# RECEPTORA_SECUNDARIA.net
KiCad netlist of a schematic drawn in Altium Designer
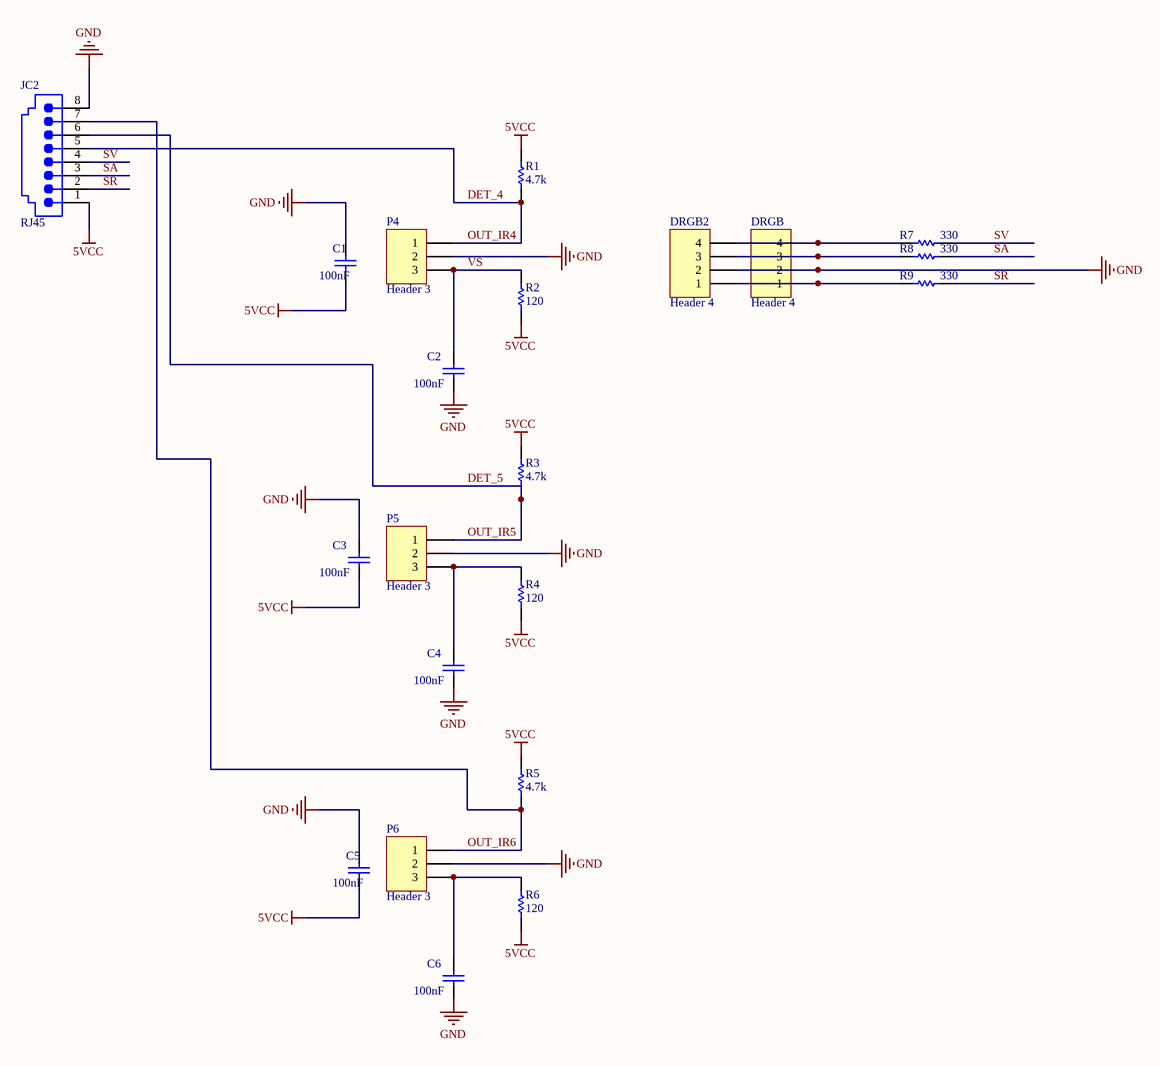
[diagram p0: RECEPTORA_SECUNDARIA.SchDoc]

(export (version "E")
  (design (tool "Eeschema 10.0.6"))
  (components
    (comp (ref "C1")
      (value "100nF")
      (footprint "VP44-2.5")
      (description "Dipped Radial Multilayer Ceramic Capacitor X7R: 220nF, 100V")
      (fields (field (name "Comment") "VP44BY224JB") (field (name "PUBLISHER") "Altium Limited"))
      (libsource (lib "Vishay Vitramon Ceramic Dipped Capacitor") (part "VP44BY224JB"))
    )
    (comp (ref "C2")
      (value "100nF")
      (footprint "VP44-2.5")
      (description "Dipped Radial Multilayer Ceramic Capacitor X7R: 220nF, 100V")
      (fields (field (name "Comment") "VP44BY224JB") (field (name "PUBLISHER") "Altium Limited"))
      (libsource (lib "Vishay Vitramon Ceramic Dipped Capacitor") (part "VP44BY224JB"))
    )
    (comp (ref "C3")
      (value "100nF")
      (footprint "VP44-2.5")
      (description "Dipped Radial Multilayer Ceramic Capacitor X7R: 220nF, 100V")
      (fields (field (name "Comment") "VP44BY224JB") (field (name "PUBLISHER") "Altium Limited"))
      (libsource (lib "Vishay Vitramon Ceramic Dipped Capacitor") (part "VP44BY224JB"))
    )
    (comp (ref "C4")
      (value "100nF")
      (footprint "VP44-2.5")
      (description "Dipped Radial Multilayer Ceramic Capacitor X7R: 220nF, 100V")
      (fields (field (name "Comment") "VP44BY224JB") (field (name "PUBLISHER") "Altium Limited"))
      (libsource (lib "Vishay Vitramon Ceramic Dipped Capacitor") (part "VP44BY224JB"))
    )
    (comp (ref "C5")
      (value "100nF")
      (footprint "VP44-2.5")
      (description "Dipped Radial Multilayer Ceramic Capacitor X7R: 220nF, 100V")
      (fields (field (name "Comment") "VP44BY224JB") (field (name "PUBLISHER") "Altium Limited"))
      (libsource (lib "Vishay Vitramon Ceramic Dipped Capacitor") (part "VP44BY224JB"))
    )
    (comp (ref "C6")
      (value "100nF")
      (footprint "VP44-2.5")
      (description "Dipped Radial Multilayer Ceramic Capacitor X7R: 220nF, 100V")
      (fields (field (name "Comment") "VP44BY224JB") (field (name "PUBLISHER") "Altium Limited"))
      (libsource (lib "Vishay Vitramon Ceramic Dipped Capacitor") (part "VP44BY224JB"))
    )
    (comp (ref "DRGB")
      (value "Header 4")
      (footprint "HDR1X4")
      (description "Header, 4-Pin")
      (fields (field (name "PUBLISHER") "Altium Limited"))
      (libsource (lib "Miscellaneous Connectors") (part "Header 4"))
    )
    (comp (ref "DRGB2")
      (value "Header 4")
      (footprint "FP_LRGB_TH")
      (description "Header, 4-Pin")
      (fields (field (name "PUBLISHER") "Altium Limited"))
      (libsource (lib "Miscellaneous Connectors") (part "Header 4"))
    )
    (comp (ref "JC2")
      (value "RJ45")
      (footprint "15-43-6233")
      (description "Right Angle, Standard Profile, RJ45-Keyed, Flange Mount PCB Jack")
      (fields (field (name "PUBLISHER") "Altium Limited"))
      (libsource (lib "Molex Modular Jack Right Angle") (part "15-43-6233"))
    )
    (comp (ref "P4")
      (value "Header 3")
      (footprint "HDR1X3")
      (description "Header, 3-Pin")
      (fields (field (name "PUBLISHER") "Altium Limited"))
      (libsource (lib "Miscellaneous Connectors") (part "Header 3"))
    )
    (comp (ref "P5")
      (value "Header 3")
      (footprint "HDR1X3")
      (description "Header, 3-Pin")
      (fields (field (name "PUBLISHER") "Altium Limited"))
      (libsource (lib "Miscellaneous Connectors") (part "Header 3"))
    )
    (comp (ref "P6")
      (value "Header 3")
      (footprint "HDR1X3")
      (description "Header, 3-Pin")
      (fields (field (name "PUBLISHER") "Altium Limited"))
      (libsource (lib "Miscellaneous Connectors") (part "Header 3"))
    )
    (comp (ref "R1")
      (value "4.7k")
      (footprint "AXIAL-0.3")
      (description "Resistor")
      (fields (field (name "Comment") "Res") (field (name "PUBLISHER") "Altium Limited"))
      (libsource (lib "Miscellaneous Devices") (part "Res1"))
    )
    (comp (ref "R2")
      (value "120")
      (footprint "AXIAL-0.3")
      (description "Resistor")
      (fields (field (name "Comment") "Res") (field (name "PUBLISHER") "Altium Limited"))
      (libsource (lib "Miscellaneous Devices") (part "Res1"))
    )
    (comp (ref "R3")
      (value "4.7k")
      (footprint "AXIAL-0.3")
      (description "Resistor")
      (fields (field (name "Comment") "Res") (field (name "PUBLISHER") "Altium Limited"))
      (libsource (lib "Miscellaneous Devices") (part "Res1"))
    )
    (comp (ref "R4")
      (value "120")
      (footprint "AXIAL-0.3")
      (description "Resistor")
      (fields (field (name "Comment") "Res") (field (name "PUBLISHER") "Altium Limited"))
      (libsource (lib "Miscellaneous Devices") (part "Res1"))
    )
    (comp (ref "R5")
      (value "4.7k")
      (footprint "AXIAL-0.3")
      (description "Resistor")
      (fields (field (name "Comment") "Res") (field (name "PUBLISHER") "Altium Limited"))
      (libsource (lib "Miscellaneous Devices") (part "Res1"))
    )
    (comp (ref "R6")
      (value "120")
      (footprint "AXIAL-0.3")
      (description "Resistor")
      (fields (field (name "Comment") "Res") (field (name "PUBLISHER") "Altium Limited"))
      (libsource (lib "Miscellaneous Devices") (part "Res1"))
    )
    (comp (ref "R7")
      (value "330")
      (footprint "AXIAL-0.3")
      (description "Resistor")
      (fields (field (name "Comment") "Res") (field (name "PUBLISHER") "Altium Limited"))
      (libsource (lib "Miscellaneous Devices") (part "Res1"))
    )
    (comp (ref "R8")
      (value "330")
      (footprint "AXIAL-0.3")
      (description "Resistor")
      (fields (field (name "Comment") "Res") (field (name "PUBLISHER") "Altium Limited"))
      (libsource (lib "Miscellaneous Devices") (part "Res1"))
    )
    (comp (ref "R9")
      (value "330")
      (footprint "AXIAL-0.3")
      (description "Resistor")
      (fields (field (name "Comment") "Res") (field (name "PUBLISHER") "Altium Limited"))
      (libsource (lib "Miscellaneous Devices") (part "Res1"))
    )
  )
  (nets
    (net (code "1") (name "/DET_4") (class "Default")
      (node (ref "JC2") (pin "5") (pinfunction "5_5") (pintype "passive"))
      (node (ref "P4") (pin "1") (pinfunction "1_1") (pintype "passive"))
      (node (ref "R1") (pin "1") (pinfunction "1_1") (pintype "passive"))
    )
    (net (code "2") (name "/DET_5") (class "Default")
      (node (ref "JC2") (pin "6") (pinfunction "6_6") (pintype "passive"))
      (node (ref "P5") (pin "1") (pinfunction "1_1") (pintype "passive"))
      (node (ref "R3") (pin "1") (pinfunction "1_1") (pintype "passive"))
    )
    (net (code "3") (name "/OUT_IR6") (class "Default")
      (node (ref "JC2") (pin "7") (pinfunction "7_7") (pintype "passive"))
      (node (ref "P6") (pin "1") (pinfunction "1_1") (pintype "passive"))
      (node (ref "R5") (pin "1") (pinfunction "1_1") (pintype "passive"))
    )
    (net (code "4") (name "/SA") (class "Default")
      (node (ref "JC2") (pin "3") (pinfunction "3_3") (pintype "passive"))
      (node (ref "R8") (pin "2") (pinfunction "2_2") (pintype "passive"))
    )
    (net (code "5") (name "/SR") (class "Default")
      (node (ref "JC2") (pin "2") (pinfunction "2_2") (pintype "passive"))
      (node (ref "R9") (pin "2") (pinfunction "2_2") (pintype "passive"))
    )
    (net (code "6") (name "/SV") (class "Default")
      (node (ref "JC2") (pin "4") (pinfunction "4_4") (pintype "passive"))
      (node (ref "R7") (pin "2") (pinfunction "2_2") (pintype "passive"))
    )
    (net (code "7") (name "/VS") (class "Default")
      (node (ref "C2") (pin "1") (pinfunction "1_1") (pintype "passive"))
      (node (ref "P4") (pin "3") (pinfunction "3_3") (pintype "passive"))
      (node (ref "R2") (pin "2") (pinfunction "2_2") (pintype "passive"))
    )
    (net (code "8") (name "5VCC") (class "Default")
      (node (ref "C1") (pin "2") (pinfunction "2_2") (pintype "passive"))
      (node (ref "C3") (pin "2") (pinfunction "2_2") (pintype "passive"))
      (node (ref "C5") (pin "2") (pinfunction "2_2") (pintype "passive"))
      (node (ref "JC2") (pin "1") (pinfunction "1_1") (pintype "passive"))
      (node (ref "R1") (pin "2") (pinfunction "2_2") (pintype "passive"))
      (node (ref "R2") (pin "1") (pinfunction "1_1") (pintype "passive"))
      (node (ref "R3") (pin "2") (pinfunction "2_2") (pintype "passive"))
      (node (ref "R4") (pin "1") (pinfunction "1_1") (pintype "passive"))
      (node (ref "R5") (pin "2") (pinfunction "2_2") (pintype "passive"))
      (node (ref "R6") (pin "1") (pinfunction "1_1") (pintype "passive"))
    )
    (net (code "9") (name "GND") (class "Default")
      (node (ref "C1") (pin "1") (pinfunction "1_1") (pintype "passive"))
      (node (ref "C2") (pin "2") (pinfunction "2_2") (pintype "passive"))
      (node (ref "C3") (pin "1") (pinfunction "1_1") (pintype "passive"))
      (node (ref "C4") (pin "2") (pinfunction "2_2") (pintype "passive"))
      (node (ref "C5") (pin "1") (pinfunction "1_1") (pintype "passive"))
      (node (ref "C6") (pin "2") (pinfunction "2_2") (pintype "passive"))
      (node (ref "DRGB") (pin "2") (pinfunction "2_2") (pintype "passive"))
      (node (ref "DRGB2") (pin "2") (pinfunction "2_2") (pintype "passive"))
      (node (ref "JC2") (pin "8") (pinfunction "8_8") (pintype "passive"))
      (node (ref "P4") (pin "2") (pinfunction "2_2") (pintype "passive"))
      (node (ref "P5") (pin "2") (pinfunction "2_2") (pintype "passive"))
      (node (ref "P6") (pin "2") (pinfunction "2_2") (pintype "passive"))
    )
    (net (code "10") (name "Net-(C4-Pad1)") (class "Default")
      (node (ref "C4") (pin "1") (pinfunction "1_1") (pintype "passive"))
      (node (ref "P5") (pin "3") (pinfunction "3_3") (pintype "passive"))
      (node (ref "R4") (pin "2") (pinfunction "2_2") (pintype "passive"))
    )
    (net (code "11") (name "Net-(C6-Pad1)") (class "Default")
      (node (ref "C6") (pin "1") (pinfunction "1_1") (pintype "passive"))
      (node (ref "P6") (pin "3") (pinfunction "3_3") (pintype "passive"))
      (node (ref "R6") (pin "2") (pinfunction "2_2") (pintype "passive"))
    )
    (net (code "12") (name "Net-(DRGB-Pad1)") (class "Default")
      (node (ref "DRGB") (pin "1") (pinfunction "1_1") (pintype "passive"))
      (node (ref "DRGB2") (pin "1") (pinfunction "1_1") (pintype "passive"))
      (node (ref "R9") (pin "1") (pinfunction "1_1") (pintype "passive"))
    )
    (net (code "13") (name "Net-(DRGB-Pad3)") (class "Default")
      (node (ref "DRGB") (pin "3") (pinfunction "3_3") (pintype "passive"))
      (node (ref "DRGB2") (pin "3") (pinfunction "3_3") (pintype "passive"))
      (node (ref "R8") (pin "1") (pinfunction "1_1") (pintype "passive"))
    )
    (net (code "14") (name "Net-(DRGB-Pad4)") (class "Default")
      (node (ref "DRGB") (pin "4") (pinfunction "4_4") (pintype "passive"))
      (node (ref "DRGB2") (pin "4") (pinfunction "4_4") (pintype "passive"))
      (node (ref "R7") (pin "1") (pinfunction "1_1") (pintype "passive"))
    )
  )
)
